# KeyInput_MG.net
KiCad netlist of a schematic drawn in Altium Designer
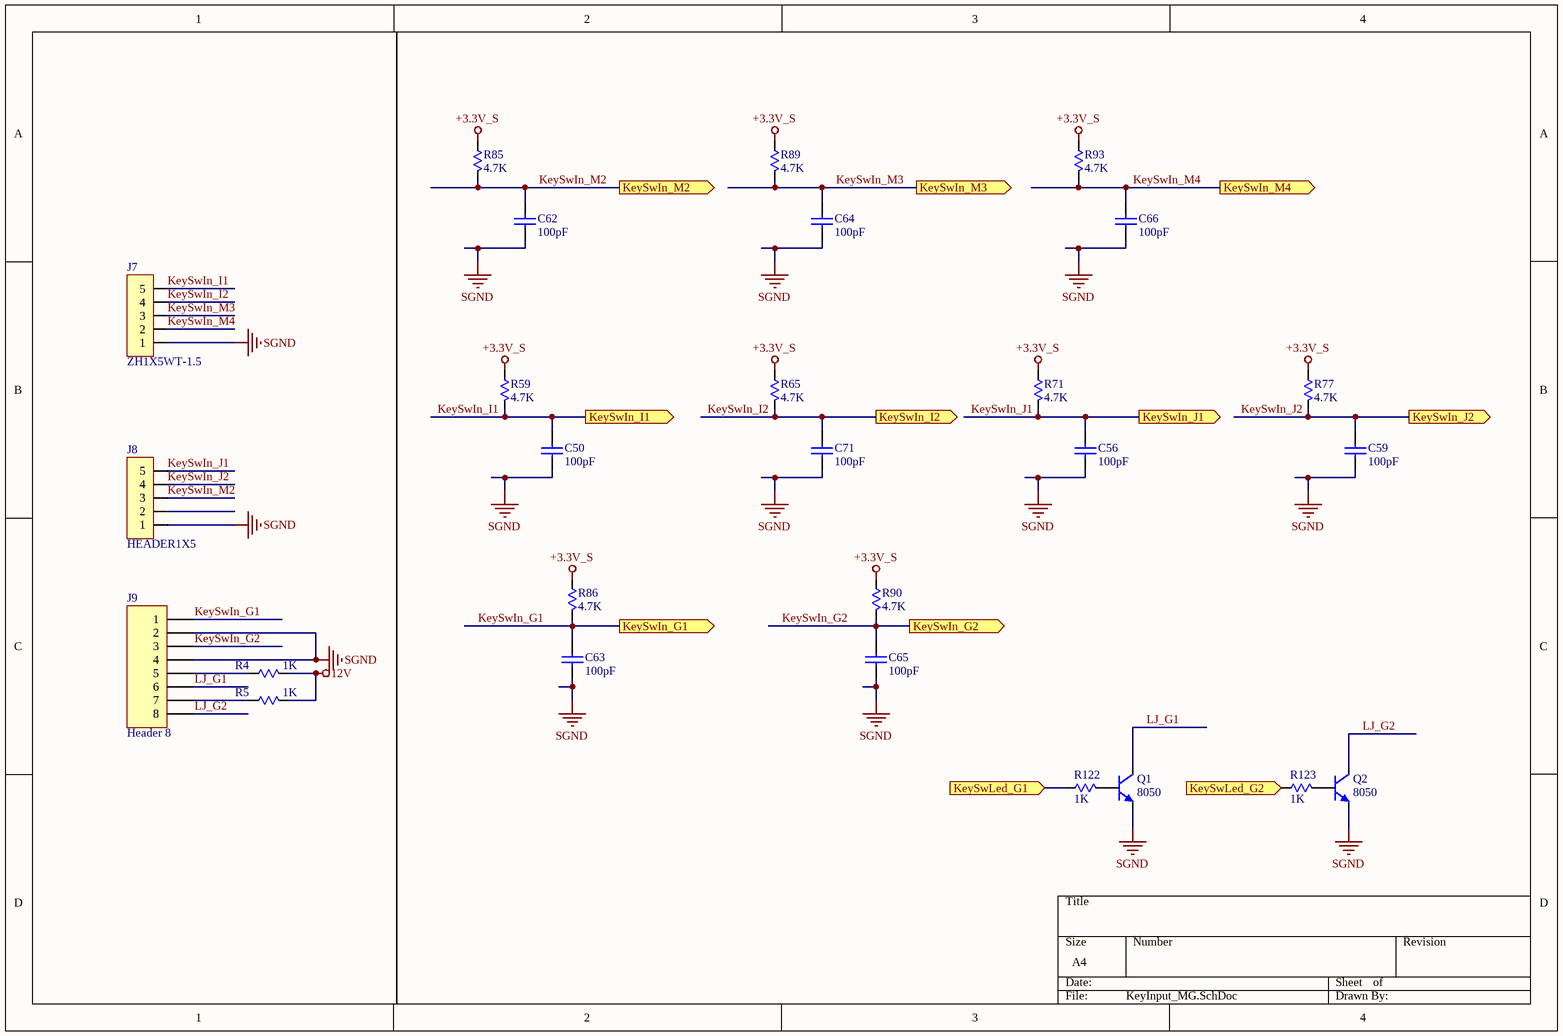
[diagram p0: KeyInput_MG.SchDoc]

(export (version "E")
  (design (tool "Eeschema 10.0.6"))
  (components
    (comp (ref "C50")
      (value "100pF")
      (footprint "C0805")
      (description "Capacitor")
      (fields (field (name "PUBLISHER") "Altium Limited"))
      (libsource (lib "Miscellaneous Devices") (part "Cap"))
    )
    (comp (ref "C56")
      (value "100pF")
      (footprint "C0805")
      (description "Capacitor")
      (fields (field (name "PUBLISHER") "Altium Limited"))
      (libsource (lib "Miscellaneous Devices") (part "Cap"))
    )
    (comp (ref "C59")
      (value "100pF")
      (footprint "C0805")
      (description "Capacitor")
      (fields (field (name "PUBLISHER") "Altium Limited"))
      (libsource (lib "Miscellaneous Devices") (part "Cap"))
    )
    (comp (ref "C62")
      (value "100pF")
      (footprint "C0805")
      (description "Capacitor")
      (fields (field (name "PUBLISHER") "Altium Limited"))
      (libsource (lib "Miscellaneous Devices") (part "Cap"))
    )
    (comp (ref "C63")
      (value "100pF")
      (footprint "C0805")
      (description "Capacitor")
      (fields (field (name "PUBLISHER") "Altium Limited"))
      (libsource (lib "Miscellaneous Devices") (part "Cap"))
    )
    (comp (ref "C64")
      (value "100pF")
      (footprint "C0805")
      (description "Capacitor")
      (fields (field (name "PUBLISHER") "Altium Limited"))
      (libsource (lib "Miscellaneous Devices") (part "Cap"))
    )
    (comp (ref "C65")
      (value "100pF")
      (footprint "C0805")
      (description "Capacitor")
      (fields (field (name "PUBLISHER") "Altium Limited"))
      (libsource (lib "Miscellaneous Devices") (part "Cap"))
    )
    (comp (ref "C66")
      (value "100pF")
      (footprint "C0805")
      (description "Capacitor")
      (fields (field (name "PUBLISHER") "Altium Limited"))
      (libsource (lib "Miscellaneous Devices") (part "Cap"))
    )
    (comp (ref "C71")
      (value "100pF")
      (footprint "C0805")
      (description "Capacitor")
      (fields (field (name "PUBLISHER") "Altium Limited"))
      (libsource (lib "Miscellaneous Devices") (part "Cap"))
    )
    (comp (ref "J7")
      (value "ZH1X5WT-1.5")
      (footprint "ZH1X5WT-1.5")
      (libsource (lib "Connector Class") (part "HEADER1X5"))
    )
    (comp (ref "J8")
      (value "HEADER1X5")
      (footprint "ZH1X5WT-1.5")
      (libsource (lib "Connector Class") (part "HEADER1X5"))
    )
    (comp (ref "J9")
      (value "Header 8")
      (footprint "ZH1X8WT-1.5")
      (description "Header, 8-Pin")
      (fields (field (name "PUBLISHER") "Altium Limited"))
      (libsource (lib "Miscellaneous Connectors") (part "Header 8"))
    )
    (comp (ref "Q1")
      (value "8050")
      (footprint "SOT-23")
      (description "NPN General Purpose Amplifier")
      (fields (field (name "PUBLISHER") "Altium Limited"))
      (libsource (lib "Bdmc4810") (part "NPN"))
    )
    (comp (ref "Q2")
      (value "8050")
      (footprint "SOT-23")
      (description "NPN General Purpose Amplifier")
      (fields (field (name "PUBLISHER") "Altium Limited"))
      (libsource (lib "Bdmc4810") (part "NPN"))
    )
    (comp (ref "R4")
      (value "1K")
      (footprint "R0805")
      (description "Resistor")
      (fields (field (name "PUBLISHER") "Altium Limited"))
      (libsource (lib "Passive Components Class") (part "RES"))
    )
    (comp (ref "R5")
      (value "1K")
      (footprint "R0805")
      (description "Resistor")
      (fields (field (name "PUBLISHER") "Altium Limited"))
      (libsource (lib "Passive Components Class") (part "RES"))
    )
    (comp (ref "R59")
      (value "4.7K")
      (footprint "R0805")
      (description "Resistor")
      (fields (field (name "PUBLISHER") "Altium Limited"))
      (libsource (lib "Passive Components Class") (part "RES"))
    )
    (comp (ref "R65")
      (value "4.7K")
      (footprint "R0805")
      (description "Resistor")
      (fields (field (name "PUBLISHER") "Altium Limited"))
      (libsource (lib "Passive Components Class") (part "RES"))
    )
    (comp (ref "R71")
      (value "4.7K")
      (footprint "R0805")
      (description "Resistor")
      (fields (field (name "PUBLISHER") "Altium Limited"))
      (libsource (lib "Passive Components Class") (part "RES"))
    )
    (comp (ref "R77")
      (value "4.7K")
      (footprint "R0805")
      (description "Resistor")
      (fields (field (name "PUBLISHER") "Altium Limited"))
      (libsource (lib "Passive Components Class") (part "RES"))
    )
    (comp (ref "R85")
      (value "4.7K")
      (footprint "R0805")
      (description "Resistor")
      (fields (field (name "PUBLISHER") "Altium Limited"))
      (libsource (lib "Passive Components Class") (part "RES"))
    )
    (comp (ref "R86")
      (value "4.7K")
      (footprint "R0805")
      (description "Resistor")
      (fields (field (name "PUBLISHER") "Altium Limited"))
      (libsource (lib "Passive Components Class") (part "RES"))
    )
    (comp (ref "R89")
      (value "4.7K")
      (footprint "R0805")
      (description "Resistor")
      (fields (field (name "PUBLISHER") "Altium Limited"))
      (libsource (lib "Passive Components Class") (part "RES"))
    )
    (comp (ref "R90")
      (value "4.7K")
      (footprint "R0805")
      (description "Resistor")
      (fields (field (name "PUBLISHER") "Altium Limited"))
      (libsource (lib "Passive Components Class") (part "RES"))
    )
    (comp (ref "R93")
      (value "4.7K")
      (footprint "R0805")
      (description "Resistor")
      (fields (field (name "PUBLISHER") "Altium Limited"))
      (libsource (lib "Passive Components Class") (part "RES"))
    )
    (comp (ref "R122")
      (value "1K")
      (footprint "R0805")
      (description "Resistor")
      (fields (field (name "PUBLISHER") "Altium Limited"))
      (libsource (lib "Passive Components Class") (part "RES"))
    )
    (comp (ref "R123")
      (value "1K")
      (footprint "R0805")
      (description "Resistor")
      (fields (field (name "PUBLISHER") "Altium Limited"))
      (libsource (lib "Passive Components Class") (part "RES"))
    )
  )
  (nets
    (net (code "1") (name "+3.3V_S") (class "Default")
      (node (ref "R59") (pin "2") (pinfunction "2_2") (pintype "passive"))
      (node (ref "R65") (pin "2") (pinfunction "2_2") (pintype "passive"))
      (node (ref "R71") (pin "2") (pinfunction "2_2") (pintype "passive"))
      (node (ref "R77") (pin "2") (pinfunction "2_2") (pintype "passive"))
      (node (ref "R85") (pin "2") (pinfunction "2_2") (pintype "passive"))
      (node (ref "R86") (pin "2") (pinfunction "2_2") (pintype "passive"))
      (node (ref "R89") (pin "2") (pinfunction "2_2") (pintype "passive"))
      (node (ref "R90") (pin "2") (pinfunction "2_2") (pintype "passive"))
      (node (ref "R93") (pin "2") (pinfunction "2_2") (pintype "passive"))
    )
    (net (code "2") (name "/KeySwIn_G1") (class "Default")
      (node (ref "C63") (pin "1") (pinfunction "1_1") (pintype "passive"))
      (node (ref "J9") (pin "1") (pinfunction "1_1") (pintype "passive"))
      (node (ref "R86") (pin "1") (pinfunction "1_1") (pintype "passive"))
    )
    (net (code "3") (name "/KeySwIn_G2") (class "Default")
      (node (ref "C65") (pin "1") (pinfunction "1_1") (pintype "passive"))
      (node (ref "J9") (pin "3") (pinfunction "3_3") (pintype "passive"))
      (node (ref "R90") (pin "1") (pinfunction "1_1") (pintype "passive"))
    )
    (net (code "4") (name "/KeySwIn_I1") (class "Default")
      (node (ref "C50") (pin "1") (pinfunction "1_1") (pintype "passive"))
      (node (ref "J7") (pin "5") (pinfunction "5_5") (pintype "passive"))
      (node (ref "R59") (pin "1") (pinfunction "1_1") (pintype "passive"))
    )
    (net (code "5") (name "/KeySwIn_I2") (class "Default")
      (node (ref "C71") (pin "1") (pinfunction "1_1") (pintype "passive"))
      (node (ref "J7") (pin "4") (pinfunction "4_4") (pintype "passive"))
      (node (ref "R65") (pin "1") (pinfunction "1_1") (pintype "passive"))
    )
    (net (code "6") (name "/KeySwIn_J1") (class "Default")
      (node (ref "C56") (pin "1") (pinfunction "1_1") (pintype "passive"))
      (node (ref "J8") (pin "5") (pinfunction "5_5") (pintype "passive"))
      (node (ref "R71") (pin "1") (pinfunction "1_1") (pintype "passive"))
    )
    (net (code "7") (name "/KeySwIn_J2") (class "Default")
      (node (ref "C59") (pin "1") (pinfunction "1_1") (pintype "passive"))
      (node (ref "J8") (pin "4") (pinfunction "4_4") (pintype "passive"))
      (node (ref "R77") (pin "1") (pinfunction "1_1") (pintype "passive"))
    )
    (net (code "8") (name "/KeySwIn_M2") (class "Default")
      (node (ref "C62") (pin "1") (pinfunction "1_1") (pintype "passive"))
      (node (ref "J8") (pin "3") (pinfunction "3_3") (pintype "passive"))
      (node (ref "R85") (pin "1") (pinfunction "1_1") (pintype "passive"))
    )
    (net (code "9") (name "/KeySwIn_M3") (class "Default")
      (node (ref "C64") (pin "1") (pinfunction "1_1") (pintype "passive"))
      (node (ref "J7") (pin "3") (pinfunction "3_3") (pintype "passive"))
      (node (ref "R89") (pin "1") (pinfunction "1_1") (pintype "passive"))
    )
    (net (code "10") (name "/KeySwIn_M4") (class "Default")
      (node (ref "C66") (pin "1") (pinfunction "1_1") (pintype "passive"))
      (node (ref "J7") (pin "2") (pinfunction "2_2") (pintype "passive"))
      (node (ref "R93") (pin "1") (pinfunction "1_1") (pintype "passive"))
    )
    (net (code "11") (name "/KeySwLed_G1") (class "Default")
      (node (ref "R122") (pin "2") (pinfunction "2_2") (pintype "passive"))
    )
    (net (code "12") (name "/KeySwLed_G2") (class "Default")
      (node (ref "R123") (pin "2") (pinfunction "2_2") (pintype "passive"))
    )
    (net (code "13") (name "/LJ_G1") (class "Default")
      (node (ref "J9") (pin "6") (pinfunction "6_6") (pintype "passive"))
      (node (ref "Q1") (pin "3") (pinfunction "C_3") (pintype "passive"))
    )
    (net (code "14") (name "/LJ_G2") (class "Default")
      (node (ref "J9") (pin "8") (pinfunction "8_8") (pintype "passive"))
      (node (ref "Q2") (pin "3") (pinfunction "C_3") (pintype "passive"))
    )
    (net (code "15") (name "12V") (class "Default")
      (node (ref "R4") (pin "1") (pinfunction "1_1") (pintype "passive"))
      (node (ref "R5") (pin "1") (pinfunction "1_1") (pintype "passive"))
    )
    (net (code "16") (name "Net-(J9-Pad5)") (class "Default")
      (node (ref "J9") (pin "5") (pinfunction "5_5") (pintype "passive"))
      (node (ref "R4") (pin "2") (pinfunction "2_2") (pintype "passive"))
    )
    (net (code "17") (name "Net-(J9-Pad7)") (class "Default")
      (node (ref "J9") (pin "7") (pinfunction "7_7") (pintype "passive"))
      (node (ref "R5") (pin "2") (pinfunction "2_2") (pintype "passive"))
    )
    (net (code "18") (name "Net-(Q1-B)") (class "Default")
      (node (ref "Q1") (pin "1") (pinfunction "B_1") (pintype "passive"))
      (node (ref "R122") (pin "1") (pinfunction "1_1") (pintype "passive"))
    )
    (net (code "19") (name "Net-(Q2-B)") (class "Default")
      (node (ref "Q2") (pin "1") (pinfunction "B_1") (pintype "passive"))
      (node (ref "R123") (pin "1") (pinfunction "1_1") (pintype "passive"))
    )
    (net (code "20") (name "SGND") (class "Default")
      (node (ref "C50") (pin "2") (pinfunction "2_2") (pintype "passive"))
      (node (ref "C56") (pin "2") (pinfunction "2_2") (pintype "passive"))
      (node (ref "C59") (pin "2") (pinfunction "2_2") (pintype "passive"))
      (node (ref "C62") (pin "2") (pinfunction "2_2") (pintype "passive"))
      (node (ref "C63") (pin "2") (pinfunction "2_2") (pintype "passive"))
      (node (ref "C64") (pin "2") (pinfunction "2_2") (pintype "passive"))
      (node (ref "C65") (pin "2") (pinfunction "2_2") (pintype "passive"))
      (node (ref "C66") (pin "2") (pinfunction "2_2") (pintype "passive"))
      (node (ref "C71") (pin "2") (pinfunction "2_2") (pintype "passive"))
      (node (ref "J7") (pin "1") (pinfunction "1_1") (pintype "passive"))
      (node (ref "J8") (pin "1") (pinfunction "1_1") (pintype "passive"))
      (node (ref "J9") (pin "2") (pinfunction "2_2") (pintype "passive"))
      (node (ref "J9") (pin "4") (pinfunction "4_4") (pintype "passive"))
      (node (ref "Q1") (pin "2") (pinfunction "E_2") (pintype "passive"))
      (node (ref "Q2") (pin "2") (pinfunction "E_2") (pintype "passive"))
    )
    (net (code "21") (name "unconnected-(J8-Pad2)") (class "Default")
      (node (ref "J8") (pin "2") (pinfunction "2_2") (pintype "passive"))
    )
  )
)
